# ESP8266-programmer.net
KiCad netlist of a schematic drawn in EAGLE
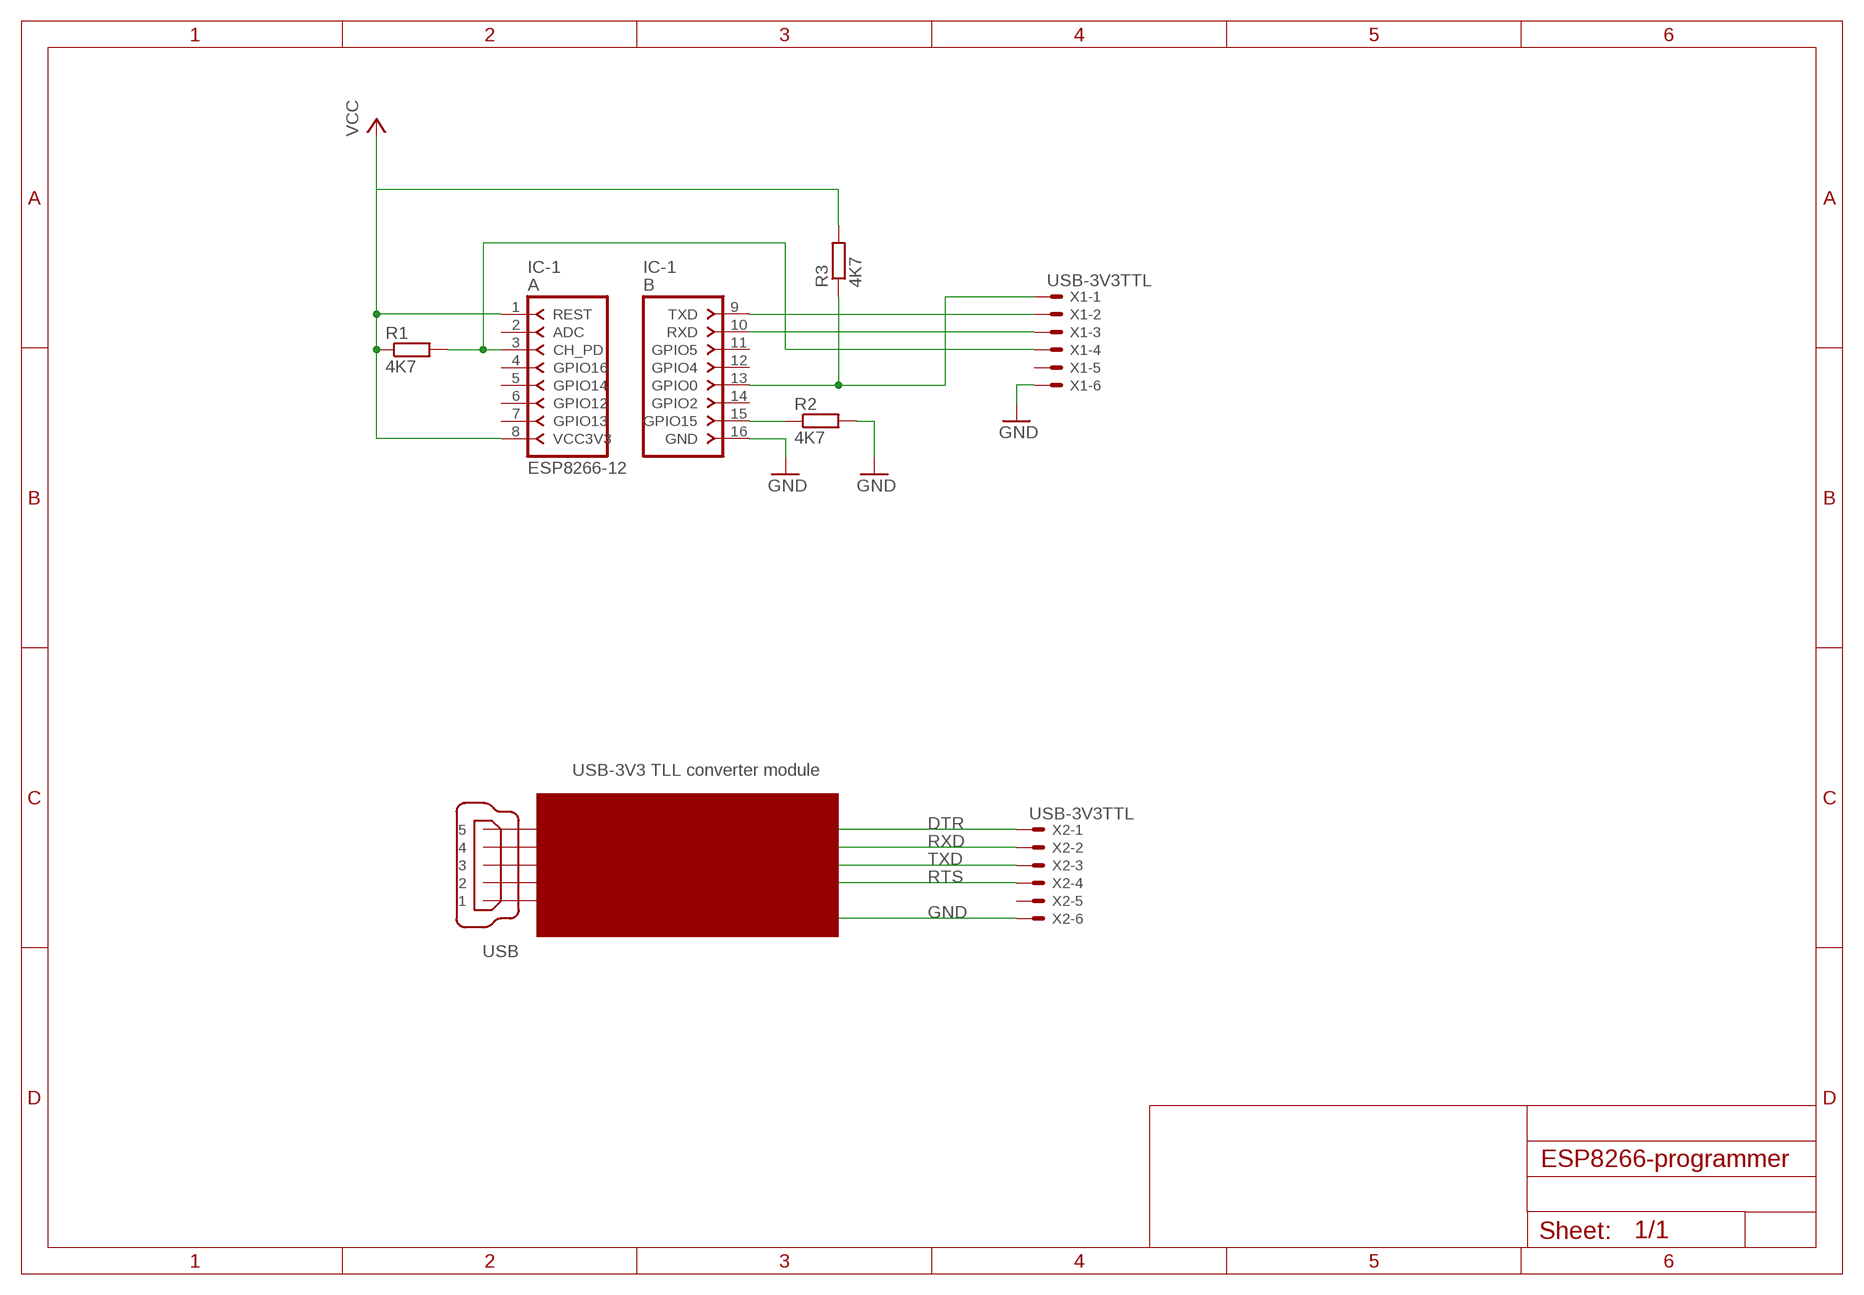
[diagram p0: schematic, sheet 1]

(export (version "E")
  (design (tool "Eeschema 10.0.6"))
  (components
    (comp (ref "IC-1")
      (value "ESP8266-12")
      (footprint "eagle-import:ESP8266-ADAPTER")
      (libsource (lib "eagle-import") (part "ESP8266-WITH-ADAPTER"))
    )
    (comp (ref "R1")
      (value "4K7")
      (footprint "eagle-import:0207_10")
      (libsource (lib "eagle-import") (part "R-EU_0207/10"))
    )
    (comp (ref "R2")
      (value "4K7")
      (footprint "eagle-import:0207_10")
      (libsource (lib "eagle-import") (part "R-EU_0207/10"))
    )
    (comp (ref "R3")
      (value "4K7")
      (footprint "eagle-import:0207_10")
      (libsource (lib "eagle-import") (part "R-EU_0207/10"))
    )
    (comp (ref "USB")
      (value "MINI-USB-32005-301")
      (footprint "eagle-import:32005-301")
      (libsource (lib "eagle-import") (part "MINI-USB-32005-301"))
    )
    (comp (ref "X1")
      (value "USB-3V3TTL")
      (footprint "eagle-import:22-23-2061")
      (fields (field (name "MF") "MOLEX") (field (name "MPN") "22-23-2061"))
      (libsource (lib "eagle-import") (part "22-23-2061"))
    )
    (comp (ref "X2")
      (value "USB-3V3TTL")
      (footprint "eagle-import:22-23-2061")
      (fields (field (name "MF") "MOLEX") (field (name "MPN") "22-23-2061"))
      (libsource (lib "eagle-import") (part "22-23-2061"))
    )
  )
  (nets
    (net (code "1") (name "GND") (class "Default")
      (node (ref "IC-1") (pin "16") (pinfunction "GND_16") (pintype "passive"))
      (node (ref "R2") (pin "2") (pinfunction "2_2") (pintype "passive"))
      (node (ref "X1") (pin "6") (pinfunction "S_6") (pintype "passive"))
    )
    (net (code "2") (name "Net-(IC-1-CH_PD)") (class "Default")
      (node (ref "IC-1") (pin "3") (pinfunction "CH_PD_3") (pintype "passive"))
      (node (ref "R1") (pin "2") (pinfunction "2_2") (pintype "passive"))
      (node (ref "X1") (pin "4") (pinfunction "S_4") (pintype "passive"))
    )
    (net (code "3") (name "Net-(IC-1-GPIO0)") (class "Default")
      (node (ref "IC-1") (pin "13") (pinfunction "GPIO0_13") (pintype "passive"))
      (node (ref "R3") (pin "1") (pinfunction "1_1") (pintype "passive"))
      (node (ref "X1") (pin "1") (pinfunction "S_1") (pintype "passive"))
    )
    (net (code "4") (name "Net-(IC-1-GPIO15)") (class "Default")
      (node (ref "IC-1") (pin "15") (pinfunction "GPIO15_15") (pintype "passive"))
      (node (ref "R2") (pin "1") (pinfunction "1_1") (pintype "passive"))
    )
    (net (code "5") (name "Net-(IC-1-RXD)") (class "Default")
      (node (ref "IC-1") (pin "10") (pinfunction "RXD_10") (pintype "passive"))
      (node (ref "X1") (pin "3") (pinfunction "S_3") (pintype "passive"))
    )
    (net (code "6") (name "Net-(IC-1-TXD)") (class "Default")
      (node (ref "IC-1") (pin "9") (pinfunction "TXD_9") (pintype "passive"))
      (node (ref "X1") (pin "2") (pinfunction "S_2") (pintype "passive"))
    )
    (net (code "7") (name "VCC") (class "Default")
      (node (ref "IC-1") (pin "1") (pinfunction "REST_1") (pintype "passive"))
      (node (ref "IC-1") (pin "8") (pinfunction "VCC3V3_8") (pintype "passive"))
      (node (ref "R1") (pin "1") (pinfunction "1_1") (pintype "passive"))
      (node (ref "R3") (pin "2") (pinfunction "2_2") (pintype "passive"))
    )
    (net (code "8") (name "unconnected-(IC-1-ADC-Pad2)") (class "Default")
      (node (ref "IC-1") (pin "2") (pinfunction "ADC_2") (pintype "passive"))
    )
    (net (code "9") (name "unconnected-(IC-1-GPIO2-Pad14)") (class "Default")
      (node (ref "IC-1") (pin "14") (pinfunction "GPIO2_14") (pintype "passive"))
    )
    (net (code "10") (name "unconnected-(IC-1-GPIO4-Pad12)") (class "Default")
      (node (ref "IC-1") (pin "12") (pinfunction "GPIO4_12") (pintype "passive"))
    )
    (net (code "11") (name "unconnected-(IC-1-GPIO5-Pad11)") (class "Default")
      (node (ref "IC-1") (pin "11") (pinfunction "GPIO5_11") (pintype "passive"))
    )
    (net (code "12") (name "unconnected-(IC-1-GPIO12-Pad6)") (class "Default")
      (node (ref "IC-1") (pin "6") (pinfunction "GPIO12_6") (pintype "passive"))
    )
    (net (code "13") (name "unconnected-(IC-1-GPIO13-Pad7)") (class "Default")
      (node (ref "IC-1") (pin "7") (pinfunction "GPIO13_7") (pintype "passive"))
    )
    (net (code "14") (name "unconnected-(IC-1-GPIO14-Pad5)") (class "Default")
      (node (ref "IC-1") (pin "5") (pinfunction "GPIO14_5") (pintype "passive"))
    )
    (net (code "15") (name "unconnected-(IC-1-GPIO16-Pad4)") (class "Default")
      (node (ref "IC-1") (pin "4") (pinfunction "GPIO16_4") (pintype "passive"))
    )
    (net (code "16") (name "unconnected-(USB-Pad1)") (class "Default")
      (node (ref "USB") (pin "1") (pinfunction "1_1") (pintype "passive"))
    )
    (net (code "17") (name "unconnected-(USB-Pad2)") (class "Default")
      (node (ref "USB") (pin "2") (pinfunction "2_2") (pintype "passive"))
    )
    (net (code "18") (name "unconnected-(USB-Pad3)") (class "Default")
      (node (ref "USB") (pin "3") (pinfunction "3_3") (pintype "passive"))
    )
    (net (code "19") (name "unconnected-(USB-Pad4)") (class "Default")
      (node (ref "USB") (pin "4") (pinfunction "4_4") (pintype "passive"))
    )
    (net (code "20") (name "unconnected-(USB-Pad5)") (class "Default")
      (node (ref "USB") (pin "5") (pinfunction "5_5") (pintype "passive"))
    )
    (net (code "21") (name "unconnected-(X1E-S-Pad5)") (class "Default")
      (node (ref "X1") (pin "5") (pinfunction "S_5") (pintype "passive"))
    )
    (net (code "22") (name "unconnected-(X2A-S-Pad1)") (class "Default")
      (node (ref "X2") (pin "1") (pinfunction "S_1") (pintype "passive"))
    )
    (net (code "23") (name "unconnected-(X2B-S-Pad2)") (class "Default")
      (node (ref "X2") (pin "2") (pinfunction "S_2") (pintype "passive"))
    )
    (net (code "24") (name "unconnected-(X2C-S-Pad3)") (class "Default")
      (node (ref "X2") (pin "3") (pinfunction "S_3") (pintype "passive"))
    )
    (net (code "25") (name "unconnected-(X2D-S-Pad4)") (class "Default")
      (node (ref "X2") (pin "4") (pinfunction "S_4") (pintype "passive"))
    )
    (net (code "26") (name "unconnected-(X2E-S-Pad5)") (class "Default")
      (node (ref "X2") (pin "5") (pinfunction "S_5") (pintype "passive"))
    )
    (net (code "27") (name "unconnected-(X2F-S-Pad6)") (class "Default")
      (node (ref "X2") (pin "6") (pinfunction "S_6") (pintype "passive"))
    )
  )
)
